# Transponder.net
KiCad netlist of a schematic drawn in EAGLE
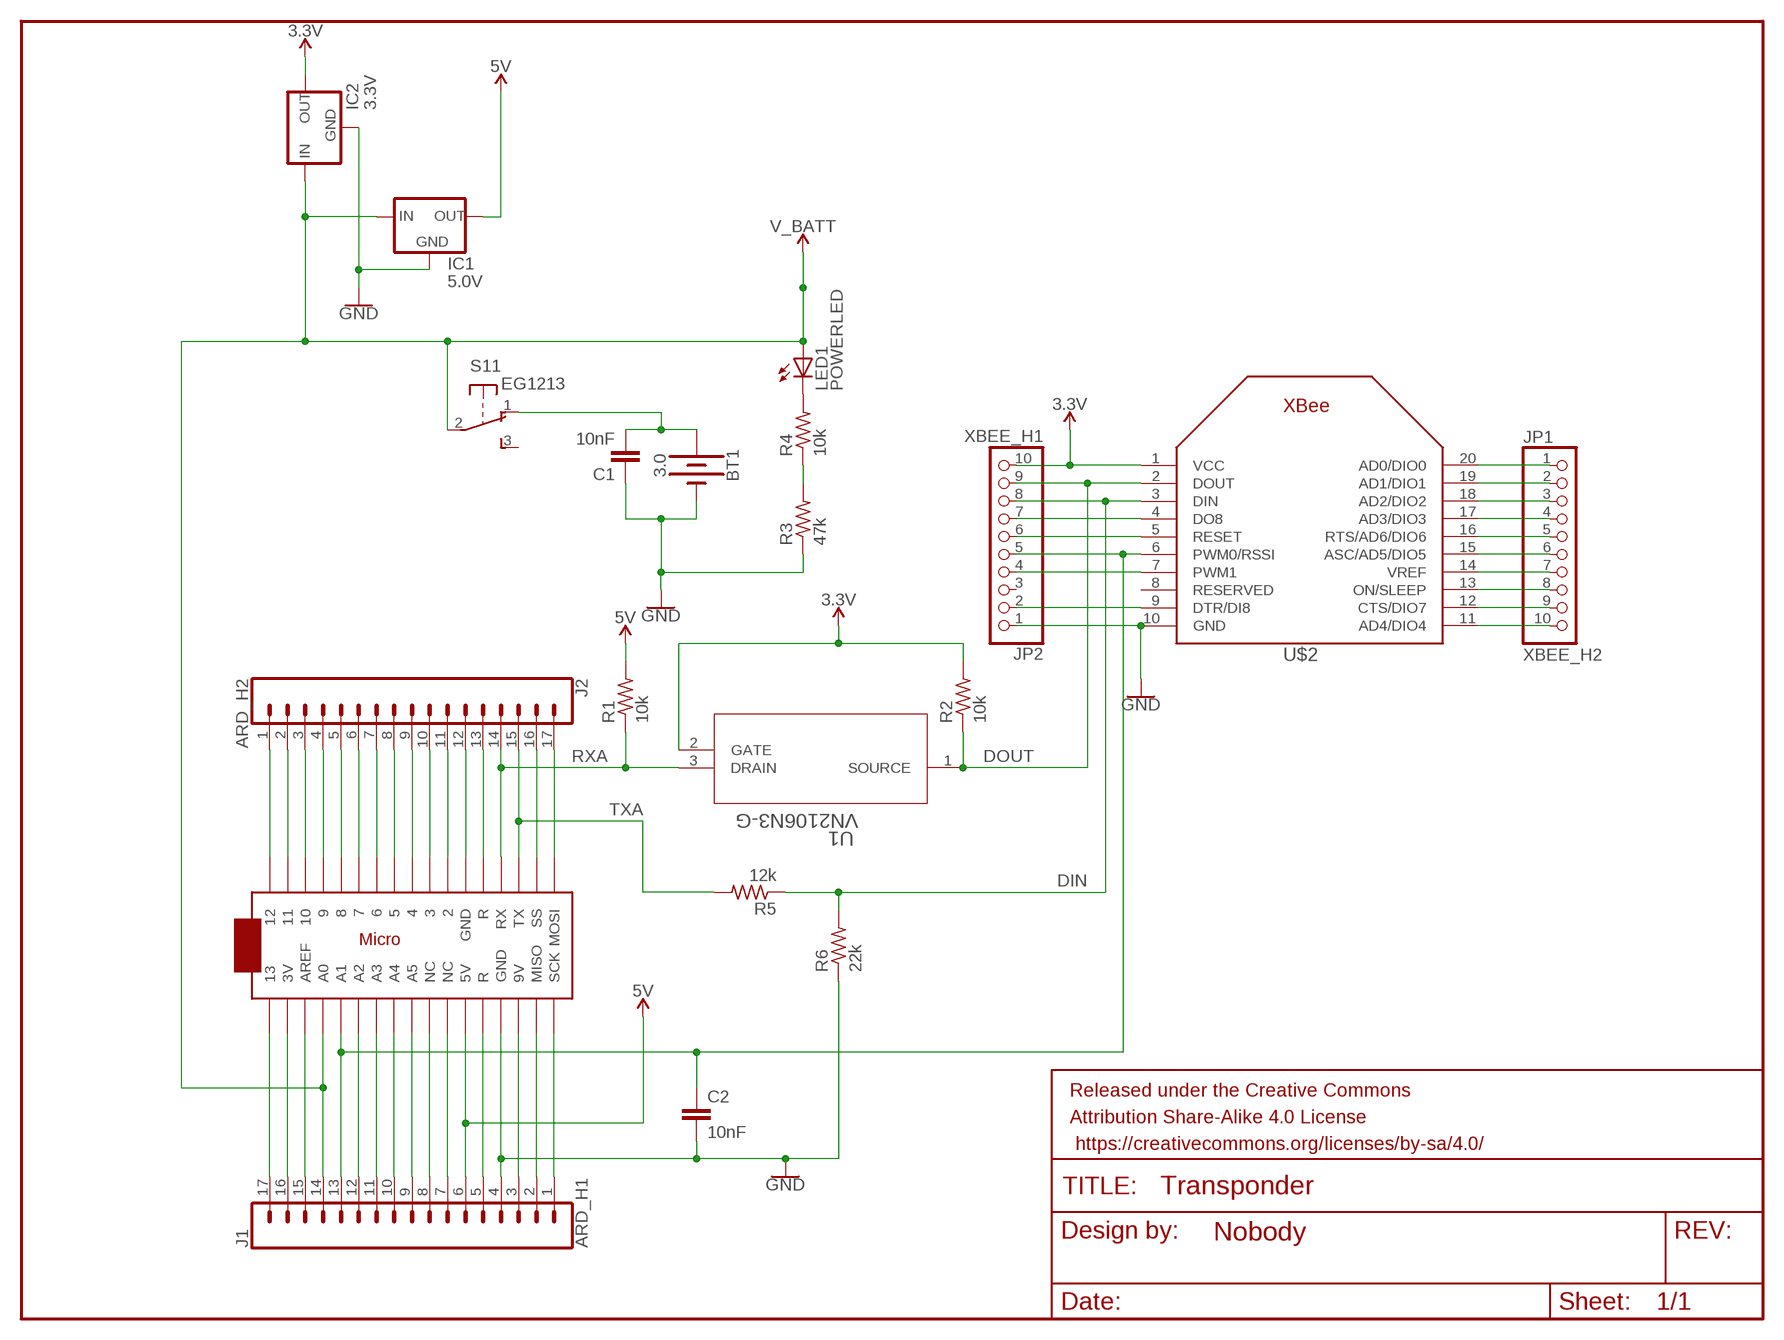
[diagram p0: schematic, sheet 1]

(export (version "E")
  (design (tool "Eeschema 10.0.6"))
  (components
    (comp (ref "BT1")
      (value "3.0")
      (footprint "eagle-import:BATTCON_20MM_4LEGS")
      (libsource (lib "eagle-import") (part "BATTERY-20MM_SMD_4LEGS"))
    )
    (comp (ref "C1")
      (value "10nF")
      (footprint "eagle-import:CAP-PTH-10MM")
      (libsource (lib "eagle-import") (part "10NF-PTH-10MM-10000V-1-%"))
    )
    (comp (ref "C2")
      (value "10nF")
      (footprint "eagle-import:CAP-PTH-10MM")
      (libsource (lib "eagle-import") (part "10NF-PTH-10MM-10000V-1-%"))
    )
    (comp (ref "FRAME1")
      (value "FRAME-LETTERNO_PACKAGE")
      (footprint "eagle-import:DUMMY")
      (fields (field (name "DESIGNER") "Nobody"))
      (libsource (lib "eagle-import") (part "FRAME-LETTERNO_PACKAGE"))
    )
    (comp (ref "IC1")
      (value "5.0V")
      (footprint "eagle-import:TO92-INLINE")
      (libsource (lib "eagle-import") (part "MCP1700INLINE"))
    )
    (comp (ref "IC2")
      (value "3.3V")
      (footprint "eagle-import:TO92-INLINE")
      (libsource (lib "eagle-import") (part "MCP1700INLINE"))
    )
    (comp (ref "J1")
      (value "ARD_H1")
      (footprint "eagle-import:1X17")
      (libsource (lib "eagle-import") (part "CONN_17"))
    )
    (comp (ref "J2")
      (value "ARD_H2")
      (footprint "eagle-import:1X17")
      (libsource (lib "eagle-import") (part "CONN_17"))
    )
    (comp (ref "JP1")
      (value "XBEE_H2")
      (footprint "eagle-import:1X10M")
      (libsource (lib "eagle-import") (part "PINHD-1X10_2.00"))
    )
    (comp (ref "JP2")
      (value "XBEE_H1")
      (footprint "eagle-import:1X10M")
      (libsource (lib "eagle-import") (part "PINHD-1X10_2.00"))
    )
    (comp (ref "LED1")
      (value "POWERLED")
      (footprint "eagle-import:LED5MM")
      (libsource (lib "eagle-import") (part "LED5MM"))
    )
    (comp (ref "R1")
      (value "10k")
      (footprint "eagle-import:0207_12")
      (libsource (lib "eagle-import") (part "R-US_0207/12"))
    )
    (comp (ref "R2")
      (value "10k")
      (footprint "eagle-import:0207_12")
      (libsource (lib "eagle-import") (part "R-US_0207/12"))
    )
    (comp (ref "R3")
      (value "47k")
      (footprint "eagle-import:0207_12")
      (libsource (lib "eagle-import") (part "R-US_0207/12"))
    )
    (comp (ref "R4")
      (value "10k")
      (footprint "eagle-import:0207_12")
      (libsource (lib "eagle-import") (part "R-US_0207/12"))
    )
    (comp (ref "R5")
      (value "12k")
      (footprint "eagle-import:0207_12")
      (libsource (lib "eagle-import") (part "R-US_0207/12"))
    )
    (comp (ref "R6")
      (value "22k")
      (footprint "eagle-import:0207_12")
      (libsource (lib "eagle-import") (part "R-US_0207/12"))
    )
    (comp (ref "S1")
      (value "EG1213")
      (footprint "eagle-import:EG1213")
      (libsource (lib "eagle-import") (part "EG1213"))
    )
    (comp (ref "U$1")
      (value "ARDUINOMICRO")
      (footprint "eagle-import:ARDUINOMICRO")
      (libsource (lib "eagle-import") (part "ARDUINOMICRO"))
    )
    (comp (ref "U$2")
      (value "XBEE")
      (footprint "eagle-import:XBEE")
      (libsource (lib "eagle-import") (part "XBEE"))
    )
    (comp (ref "U1")
      (value "VN2106N3-G")
      (footprint "eagle-import:TO-92_MC")
      (fields (field (name "COPYRIGHT") "Copyright (C) 2018 Accelerated Designs. All rights reserved"))
      (libsource (lib "eagle-import") (part "VN2106N3-G"))
    )
  )
  (nets
    (net (code "1") (name "/DIN") (class "Default")
      (node (ref "JP2") (pin "8") (pinfunction "8_8") (pintype "passive"))
      (node (ref "R5") (pin "1") (pinfunction "1_1") (pintype "passive"))
      (node (ref "R6") (pin "2") (pinfunction "2_2") (pintype "passive"))
      (node (ref "U$2") (pin "3") (pinfunction "DIN_3") (pintype "input"))
    )
    (net (code "2") (name "/DOUT") (class "Default")
      (node (ref "JP2") (pin "9") (pinfunction "9_9") (pintype "passive"))
      (node (ref "R2") (pin "1") (pinfunction "1_1") (pintype "passive"))
      (node (ref "U$2") (pin "2") (pinfunction "DOUT_2") (pintype "output"))
      (node (ref "U1") (pin "1") (pinfunction "SOURCE_1") (pintype "passive"))
    )
    (net (code "3") (name "/RXA") (class "Default")
      (node (ref "J2") (pin "14") (pinfunction "14_14") (pintype "passive"))
      (node (ref "R1") (pin "1") (pinfunction "1_1") (pintype "passive"))
      (node (ref "U$1") (pin "P$14") (pinfunction "RX_P$14") (pintype "bidirectional"))
      (node (ref "U1") (pin "3") (pinfunction "DRAIN_3") (pintype "passive"))
    )
    (net (code "4") (name "/TXA") (class "Default")
      (node (ref "J2") (pin "15") (pinfunction "15_15") (pintype "passive"))
      (node (ref "R5") (pin "2") (pinfunction "2_2") (pintype "passive"))
      (node (ref "U$1") (pin "P$15") (pinfunction "TX_P$15") (pintype "bidirectional"))
    )
    (net (code "5") (name "3.3V") (class "Default")
      (node (ref "IC2") (pin "3") (pinfunction "OUT_3") (pintype "passive"))
      (node (ref "JP2") (pin "10") (pinfunction "10_10") (pintype "passive"))
      (node (ref "R2") (pin "2") (pinfunction "2_2") (pintype "passive"))
      (node (ref "U$2") (pin "1") (pinfunction "VCC_1") (pintype "power_in"))
      (node (ref "U1") (pin "2") (pinfunction "GATE_2") (pintype "passive"))
    )
    (net (code "6") (name "5V") (class "Default")
      (node (ref "IC1") (pin "3") (pinfunction "OUT_3") (pintype "passive"))
      (node (ref "J1") (pin "6") (pinfunction "6_6") (pintype "passive"))
      (node (ref "R1") (pin "2") (pinfunction "2_2") (pintype "passive"))
      (node (ref "U$1") (pin "P$23") (pinfunction "5V_P$23") (pintype "bidirectional"))
    )
    (net (code "7") (name "GND") (class "Default")
      (node (ref "BT1") (pin "NEGATIVE") (pinfunction "-_NEGATIVE") (pintype "power_in"))
      (node (ref "C1") (pin "1") (pinfunction "1_1") (pintype "passive"))
      (node (ref "C2") (pin "2") (pinfunction "2_2") (pintype "passive"))
      (node (ref "IC1") (pin "1") (pinfunction "GND_1") (pintype "input"))
      (node (ref "IC2") (pin "1") (pinfunction "GND_1") (pintype "input"))
      (node (ref "J1") (pin "4") (pinfunction "4_4") (pintype "passive"))
      (node (ref "JP2") (pin "1") (pinfunction "1_1") (pintype "passive"))
      (node (ref "R3") (pin "1") (pinfunction "1_1") (pintype "passive"))
      (node (ref "R6") (pin "1") (pinfunction "1_1") (pintype "passive"))
      (node (ref "U$1") (pin "P$12") (pinfunction "GND_P$12") (pintype "bidirectional"))
      (node (ref "U$2") (pin "10") (pinfunction "GND_10") (pintype "power_in"))
    )
    (net (code "8") (name "Net-(J1-Pad5)") (class "Default")
      (node (ref "J1") (pin "5") (pinfunction "5_5") (pintype "passive"))
      (node (ref "U$1") (pin "P$13") (pinfunction "R_P$13") (pintype "bidirectional"))
    )
    (net (code "9") (name "Net-(J1-Pad7)") (class "Default")
      (node (ref "J1") (pin "7") (pinfunction "7_7") (pintype "passive"))
      (node (ref "U$1") (pin "P$24") (pinfunction "NC_P$24") (pintype "bidirectional"))
    )
    (net (code "10") (name "Net-(J1-Pad8)") (class "Default")
      (node (ref "J1") (pin "8") (pinfunction "8_8") (pintype "passive"))
      (node (ref "U$1") (pin "P$25") (pinfunction "NC_P$25") (pintype "bidirectional"))
    )
    (net (code "11") (name "Net-(J2-Pad12)") (class "Default")
      (node (ref "J2") (pin "12") (pinfunction "12_12") (pintype "passive"))
      (node (ref "U$1") (pin "P$21") (pinfunction "GND_P$21") (pintype "bidirectional"))
    )
    (net (code "12") (name "Net-(J2-Pad13)") (class "Default")
      (node (ref "J2") (pin "13") (pinfunction "13_13") (pintype "passive"))
      (node (ref "U$1") (pin "P$22") (pinfunction "R_P$22") (pintype "bidirectional"))
    )
    (net (code "13") (name "Net-(LED1-C)") (class "Default")
      (node (ref "LED1") (pin "K") (pinfunction "C_K") (pintype "passive"))
      (node (ref "R4") (pin "2") (pinfunction "2_2") (pintype "passive"))
    )
    (net (code "14") (name "Net-(R3-Pad2)") (class "Default")
      (node (ref "R3") (pin "2") (pinfunction "2_2") (pintype "passive"))
      (node (ref "R4") (pin "1") (pinfunction "1_1") (pintype "passive"))
    )
    (net (code "15") (name "Net-(S1A-O)") (class "Default")
      (node (ref "BT1") (pin "POSITIVE@1") (pinfunction "+_POSITIVE@1") (pintype "power_in"))
      (node (ref "BT1") (pin "POSITIVE@2") (pinfunction "+_POSITIVE@2") (pintype "power_in"))
      (node (ref "BT1") (pin "POSITIVE@3") (pinfunction "+_POSITIVE@3") (pintype "power_in"))
      (node (ref "BT1") (pin "POSITIVE@4") (pinfunction "+_POSITIVE@4") (pintype "power_in"))
      (node (ref "C1") (pin "2") (pinfunction "2_2") (pintype "passive"))
      (node (ref "S1") (pin "1") (pinfunction "O_1") (pintype "passive"))
    )
    (net (code "16") (name "Net-(U$1-2)") (class "Default")
      (node (ref "J2") (pin "11") (pinfunction "11_11") (pintype "passive"))
      (node (ref "U$1") (pin "P$11") (pinfunction "2_P$11") (pintype "bidirectional"))
    )
    (net (code "17") (name "Net-(U$1-3)") (class "Default")
      (node (ref "J2") (pin "10") (pinfunction "10_10") (pintype "passive"))
      (node (ref "U$1") (pin "P$10") (pinfunction "3_P$10") (pintype "bidirectional"))
    )
    (net (code "18") (name "Net-(U$1-3V)") (class "Default")
      (node (ref "J1") (pin "16") (pinfunction "16_16") (pintype "passive"))
      (node (ref "U$1") (pin "P$33") (pinfunction "3V_P$33") (pintype "bidirectional"))
    )
    (net (code "19") (name "Net-(U$1-4)") (class "Default")
      (node (ref "J2") (pin "9") (pinfunction "9_9") (pintype "passive"))
      (node (ref "U$1") (pin "P$9") (pinfunction "4_P$9") (pintype "bidirectional"))
    )
    (net (code "20") (name "Net-(U$1-5)") (class "Default")
      (node (ref "J2") (pin "8") (pinfunction "8_8") (pintype "passive"))
      (node (ref "U$1") (pin "P$8") (pinfunction "5_P$8") (pintype "bidirectional"))
    )
    (net (code "21") (name "Net-(U$1-6)") (class "Default")
      (node (ref "J2") (pin "7") (pinfunction "7_7") (pintype "passive"))
      (node (ref "U$1") (pin "P$7") (pinfunction "6_P$7") (pintype "bidirectional"))
    )
    (net (code "22") (name "Net-(U$1-7)") (class "Default")
      (node (ref "J2") (pin "6") (pinfunction "6_6") (pintype "passive"))
      (node (ref "U$1") (pin "P$6") (pinfunction "7_P$6") (pintype "bidirectional"))
    )
    (net (code "23") (name "Net-(U$1-8)") (class "Default")
      (node (ref "J2") (pin "5") (pinfunction "5_5") (pintype "passive"))
      (node (ref "U$1") (pin "P$5") (pinfunction "8_P$5") (pintype "bidirectional"))
    )
    (net (code "24") (name "Net-(U$1-9)") (class "Default")
      (node (ref "J2") (pin "4") (pinfunction "4_4") (pintype "passive"))
      (node (ref "U$1") (pin "P$4") (pinfunction "9_P$4") (pintype "bidirectional"))
    )
    (net (code "25") (name "Net-(U$1-9V)") (class "Default")
      (node (ref "J1") (pin "3") (pinfunction "3_3") (pintype "passive"))
      (node (ref "U$1") (pin "P$20") (pinfunction "9V_P$20") (pintype "bidirectional"))
    )
    (net (code "26") (name "Net-(U$1-10)") (class "Default")
      (node (ref "J2") (pin "3") (pinfunction "3_3") (pintype "passive"))
      (node (ref "U$1") (pin "P$3") (pinfunction "10_P$3") (pintype "bidirectional"))
    )
    (net (code "27") (name "Net-(U$1-11)") (class "Default")
      (node (ref "J2") (pin "2") (pinfunction "2_2") (pintype "passive"))
      (node (ref "U$1") (pin "P$2") (pinfunction "11_P$2") (pintype "bidirectional"))
    )
    (net (code "28") (name "Net-(U$1-12)") (class "Default")
      (node (ref "J2") (pin "1") (pinfunction "1_1") (pintype "passive"))
      (node (ref "U$1") (pin "P$1") (pinfunction "12_P$1") (pintype "bidirectional"))
    )
    (net (code "29") (name "Net-(U$1-13)") (class "Default")
      (node (ref "J1") (pin "17") (pinfunction "17_17") (pintype "passive"))
      (node (ref "U$1") (pin "P$34") (pinfunction "13_P$34") (pintype "bidirectional"))
    )
    (net (code "30") (name "Net-(U$1-A1)") (class "Default")
      (node (ref "C2") (pin "1") (pinfunction "1_1") (pintype "passive"))
      (node (ref "J1") (pin "13") (pinfunction "13_13") (pintype "passive"))
      (node (ref "JP2") (pin "5") (pinfunction "5_5") (pintype "passive"))
      (node (ref "U$1") (pin "P$30") (pinfunction "A1_P$30") (pintype "bidirectional"))
      (node (ref "U$2") (pin "6") (pinfunction "PWM0/RSSI_6") (pintype "output"))
    )
    (net (code "31") (name "Net-(U$1-A2)") (class "Default")
      (node (ref "J1") (pin "12") (pinfunction "12_12") (pintype "passive"))
      (node (ref "U$1") (pin "P$29") (pinfunction "A2_P$29") (pintype "bidirectional"))
    )
    (net (code "32") (name "Net-(U$1-A3)") (class "Default")
      (node (ref "J1") (pin "11") (pinfunction "11_11") (pintype "passive"))
      (node (ref "U$1") (pin "P$28") (pinfunction "A3_P$28") (pintype "bidirectional"))
    )
    (net (code "33") (name "Net-(U$1-A4)") (class "Default")
      (node (ref "J1") (pin "10") (pinfunction "10_10") (pintype "passive"))
      (node (ref "U$1") (pin "P$27") (pinfunction "A4_P$27") (pintype "bidirectional"))
    )
    (net (code "34") (name "Net-(U$1-A5)") (class "Default")
      (node (ref "J1") (pin "9") (pinfunction "9_9") (pintype "passive"))
      (node (ref "U$1") (pin "P$26") (pinfunction "A5_P$26") (pintype "bidirectional"))
    )
    (net (code "35") (name "Net-(U$1-AREF)") (class "Default")
      (node (ref "J1") (pin "15") (pinfunction "15_15") (pintype "passive"))
      (node (ref "U$1") (pin "P$32") (pinfunction "AREF_P$32") (pintype "bidirectional"))
    )
    (net (code "36") (name "Net-(U$1-MISO)") (class "Default")
      (node (ref "J1") (pin "2") (pinfunction "2_2") (pintype "passive"))
      (node (ref "U$1") (pin "P$19") (pinfunction "MISO_P$19") (pintype "bidirectional"))
    )
    (net (code "37") (name "Net-(U$1-MOSI)") (class "Default")
      (node (ref "J2") (pin "17") (pinfunction "17_17") (pintype "passive"))
      (node (ref "U$1") (pin "P$17") (pinfunction "MOSI_P$17") (pintype "bidirectional"))
    )
    (net (code "38") (name "Net-(U$1-SCK)") (class "Default")
      (node (ref "J1") (pin "1") (pinfunction "1_1") (pintype "passive"))
      (node (ref "U$1") (pin "P$18") (pinfunction "SCK_P$18") (pintype "bidirectional"))
    )
    (net (code "39") (name "Net-(U$1-SS)") (class "Default")
      (node (ref "J2") (pin "16") (pinfunction "16_16") (pintype "passive"))
      (node (ref "U$1") (pin "P$16") (pinfunction "SS_P$16") (pintype "bidirectional"))
    )
    (net (code "40") (name "Net-(U$2-AD0{slash}DIO0)") (class "Default")
      (node (ref "JP1") (pin "1") (pinfunction "1_1") (pintype "passive"))
      (node (ref "U$2") (pin "20") (pinfunction "AD0/DIO0_20") (pintype "bidirectional"))
    )
    (net (code "41") (name "Net-(U$2-AD1{slash}DIO1)") (class "Default")
      (node (ref "JP1") (pin "2") (pinfunction "2_2") (pintype "passive"))
      (node (ref "U$2") (pin "19") (pinfunction "AD1/DIO1_19") (pintype "bidirectional"))
    )
    (net (code "42") (name "Net-(U$2-AD2{slash}DIO2)") (class "Default")
      (node (ref "JP1") (pin "3") (pinfunction "3_3") (pintype "passive"))
      (node (ref "U$2") (pin "18") (pinfunction "AD2/DIO2_18") (pintype "bidirectional"))
    )
    (net (code "43") (name "Net-(U$2-AD3{slash}DIO3)") (class "Default")
      (node (ref "JP1") (pin "4") (pinfunction "4_4") (pintype "passive"))
      (node (ref "U$2") (pin "17") (pinfunction "AD3/DIO3_17") (pintype "bidirectional"))
    )
    (net (code "44") (name "Net-(U$2-AD4{slash}DIO4)") (class "Default")
      (node (ref "JP1") (pin "10") (pinfunction "10_10") (pintype "passive"))
      (node (ref "U$2") (pin "11") (pinfunction "AD4/DIO4_11") (pintype "bidirectional"))
    )
    (net (code "45") (name "Net-(U$2-ASC{slash}AD5{slash}DIO5)") (class "Default")
      (node (ref "JP1") (pin "6") (pinfunction "6_6") (pintype "passive"))
      (node (ref "U$2") (pin "15") (pinfunction "ASC/AD5/DIO5_15") (pintype "bidirectional"))
    )
    (net (code "46") (name "Net-(U$2-CTS{slash}DIO7)") (class "Default")
      (node (ref "JP1") (pin "9") (pinfunction "9_9") (pintype "passive"))
      (node (ref "U$2") (pin "12") (pinfunction "CTS/DIO7_12") (pintype "bidirectional"))
    )
    (net (code "47") (name "Net-(U$2-DO8)") (class "Default")
      (node (ref "JP2") (pin "7") (pinfunction "7_7") (pintype "passive"))
      (node (ref "U$2") (pin "4") (pinfunction "DO8_4") (pintype "output"))
    )
    (net (code "48") (name "Net-(U$2-DTR{slash}DI8)") (class "Default")
      (node (ref "JP2") (pin "2") (pinfunction "2_2") (pintype "passive"))
      (node (ref "U$2") (pin "9") (pinfunction "DTR/DI8_9") (pintype "input"))
    )
    (net (code "49") (name "Net-(U$2-ON{slash}SLEEP)") (class "Default")
      (node (ref "JP1") (pin "8") (pinfunction "8_8") (pintype "passive"))
      (node (ref "U$2") (pin "13") (pinfunction "ON/SLEEP_13") (pintype "output"))
    )
    (net (code "50") (name "Net-(U$2-PWM1)") (class "Default")
      (node (ref "JP2") (pin "4") (pinfunction "4_4") (pintype "passive"))
      (node (ref "U$2") (pin "7") (pinfunction "PWM1_7") (pintype "output"))
    )
    (net (code "51") (name "Net-(U$2-RESET)") (class "Default")
      (node (ref "JP2") (pin "6") (pinfunction "6_6") (pintype "passive"))
      (node (ref "U$2") (pin "5") (pinfunction "RESET_5") (pintype "input"))
    )
    (net (code "52") (name "Net-(U$2-RTS{slash}AD6{slash}DIO6)") (class "Default")
      (node (ref "JP1") (pin "5") (pinfunction "5_5") (pintype "passive"))
      (node (ref "U$2") (pin "16") (pinfunction "RTS/AD6/DIO6_16") (pintype "bidirectional"))
    )
    (net (code "53") (name "Net-(U$2-VREF)") (class "Default")
      (node (ref "JP1") (pin "7") (pinfunction "7_7") (pintype "passive"))
      (node (ref "U$2") (pin "14") (pinfunction "VREF_14") (pintype "input"))
    )
    (net (code "54") (name "V_BATT") (class "Default")
      (node (ref "IC1") (pin "2") (pinfunction "IN_2") (pintype "input"))
      (node (ref "IC2") (pin "2") (pinfunction "IN_2") (pintype "input"))
      (node (ref "J1") (pin "14") (pinfunction "14_14") (pintype "passive"))
      (node (ref "LED1") (pin "A") (pinfunction "A_A") (pintype "passive"))
      (node (ref "S1") (pin "2") (pinfunction "P_2") (pintype "passive"))
      (node (ref "U$1") (pin "P$31") (pinfunction "A0_P$31") (pintype "bidirectional"))
    )
    (net (code "55") (name "unconnected-(JP2-Pad3)") (class "Default")
      (node (ref "JP2") (pin "3") (pinfunction "3_3") (pintype "passive"))
    )
    (net (code "56") (name "unconnected-(S1A-S-Pad3)") (class "Default")
      (node (ref "S1") (pin "3") (pinfunction "S_3") (pintype "passive"))
    )
    (net (code "57") (name "unconnected-(U$2-RESERVED-Pad8)") (class "Default")
      (node (ref "U$2") (pin "8") (pinfunction "RESERVED_8") (pintype "no_connect"))
    )
  )
)
